# PGTNX05_daisy.net
KiCad netlist of a schematic drawn in EAGLE
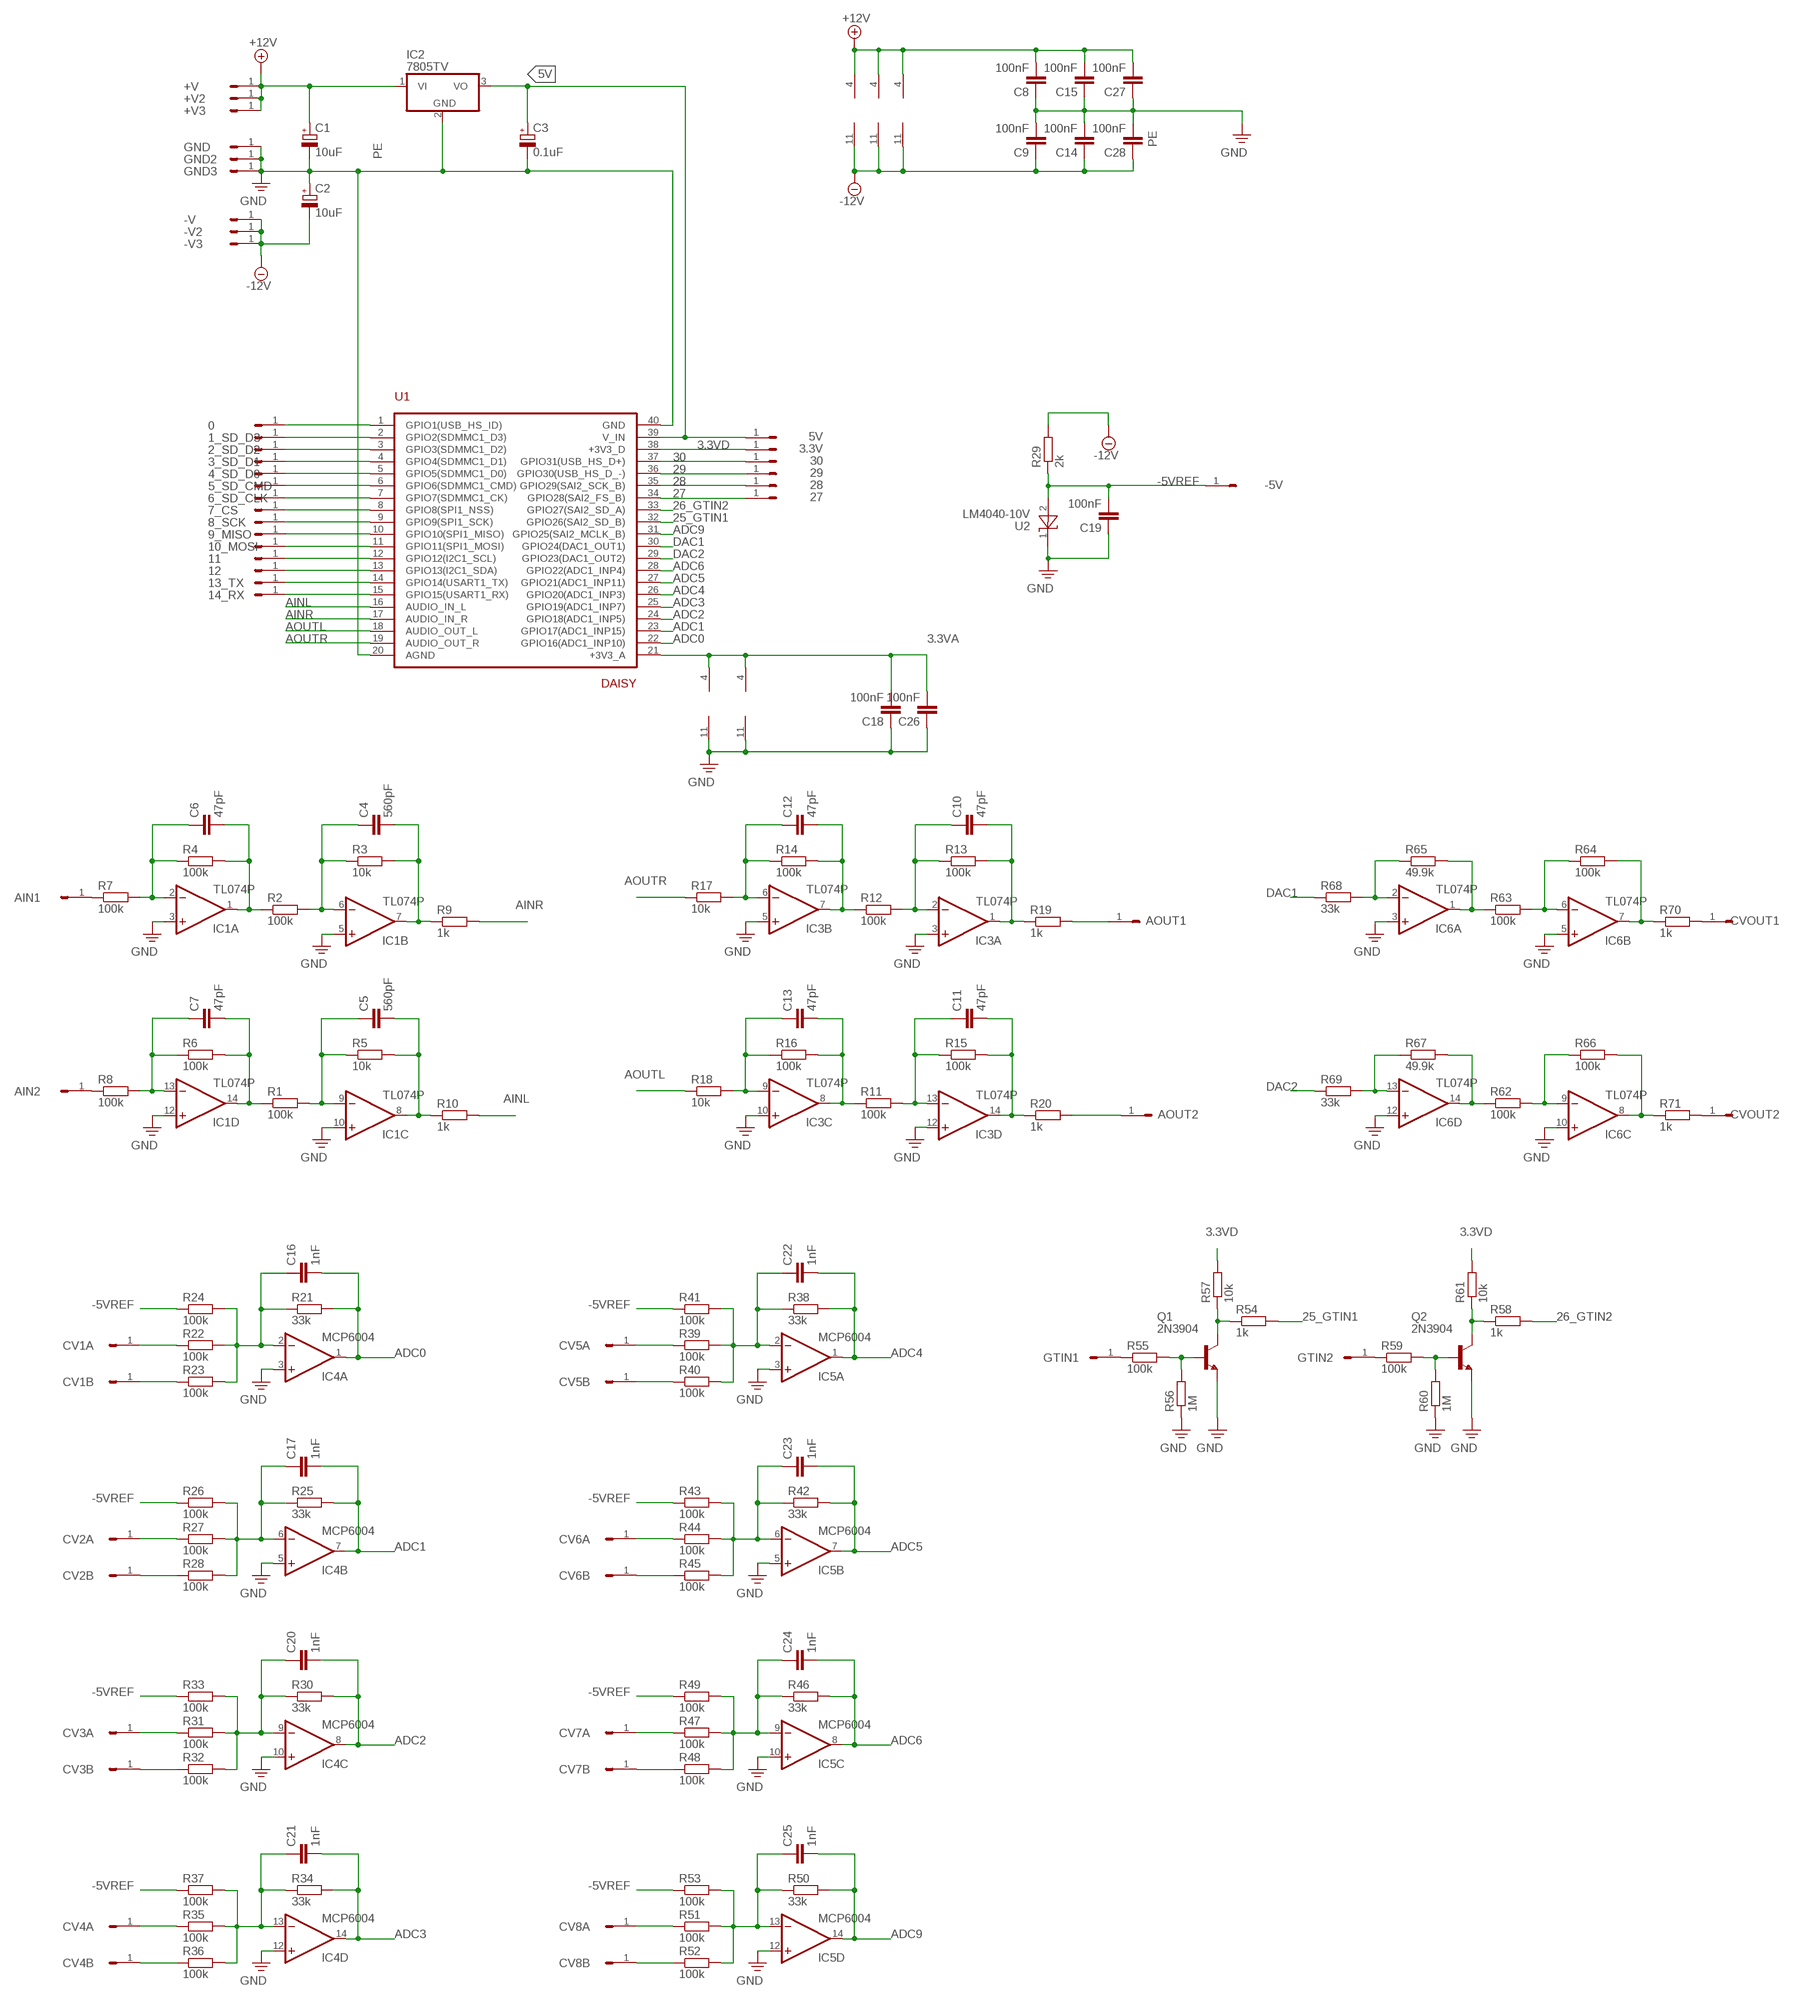
[diagram p0: schematic, sheet 1]

(export (version "E")
  (design (tool "Eeschema 10.0.6"))
  (components
    (comp (ref "+V")
      (value "HEADER/MALE/01")
      (footprint "eagle-import:HEADER_MALE_01")
      (fields (field (name "SPICEPREFIX") "X"))
      (libsource (lib "eagle-import") (part "HEADER/MALE/01"))
    )
    (comp (ref "+V2")
      (value "HEADER/MALE/01")
      (footprint "eagle-import:HEADER_MALE_01")
      (fields (field (name "SPICEPREFIX") "X"))
      (libsource (lib "eagle-import") (part "HEADER/MALE/01"))
    )
    (comp (ref "+V3")
      (value "HEADER/MALE/01")
      (footprint "eagle-import:HEADER_MALE_01")
      (fields (field (name "SPICEPREFIX") "X"))
      (libsource (lib "eagle-import") (part "HEADER/MALE/01"))
    )
    (comp (ref "-5V")
      (value "HEADER/MALE/01")
      (footprint "eagle-import:HEADER_MALE_01")
      (fields (field (name "SPICEPREFIX") "X"))
      (libsource (lib "eagle-import") (part "HEADER/MALE/01"))
    )
    (comp (ref "-V")
      (value "HEADER/MALE/01")
      (footprint "eagle-import:HEADER_MALE_01")
      (fields (field (name "SPICEPREFIX") "X"))
      (libsource (lib "eagle-import") (part "HEADER/MALE/01"))
    )
    (comp (ref "-V2")
      (value "HEADER/MALE/01")
      (footprint "eagle-import:HEADER_MALE_01")
      (fields (field (name "SPICEPREFIX") "X"))
      (libsource (lib "eagle-import") (part "HEADER/MALE/01"))
    )
    (comp (ref "-V3")
      (value "HEADER/MALE/01")
      (footprint "eagle-import:HEADER_MALE_01")
      (fields (field (name "SPICEPREFIX") "X"))
      (libsource (lib "eagle-import") (part "HEADER/MALE/01"))
    )
    (comp (ref "0")
      (value "HEADER/MALE/01")
      (footprint "eagle-import:HEADER_MALE_01")
      (fields (field (name "SPICEPREFIX") "X"))
      (libsource (lib "eagle-import") (part "HEADER/MALE/01"))
    )
    (comp (ref "1_SD_D3")
      (value "HEADER/MALE/01")
      (footprint "eagle-import:HEADER_MALE_01")
      (fields (field (name "SPICEPREFIX") "X"))
      (libsource (lib "eagle-import") (part "HEADER/MALE/01"))
    )
    (comp (ref "2_SD_D2")
      (value "HEADER/MALE/01")
      (footprint "eagle-import:HEADER_MALE_01")
      (fields (field (name "SPICEPREFIX") "X"))
      (libsource (lib "eagle-import") (part "HEADER/MALE/01"))
    )
    (comp (ref "3.3V")
      (value "HEADER/MALE/01")
      (footprint "eagle-import:HEADER_MALE_01")
      (fields (field (name "SPICEPREFIX") "X"))
      (libsource (lib "eagle-import") (part "HEADER/MALE/01"))
    )
    (comp (ref "3_SD_D1")
      (value "HEADER/MALE/01")
      (footprint "eagle-import:HEADER_MALE_01")
      (fields (field (name "SPICEPREFIX") "X"))
      (libsource (lib "eagle-import") (part "HEADER/MALE/01"))
    )
    (comp (ref "4_SD_D0")
      (value "HEADER/MALE/01")
      (footprint "eagle-import:HEADER_MALE_01")
      (fields (field (name "SPICEPREFIX") "X"))
      (libsource (lib "eagle-import") (part "HEADER/MALE/01"))
    )
    (comp (ref "5V")
      (value "HEADER/MALE/01")
      (footprint "eagle-import:HEADER_MALE_01")
      (fields (field (name "SPICEPREFIX") "X"))
      (libsource (lib "eagle-import") (part "HEADER/MALE/01"))
    )
    (comp (ref "5_SD_CMD")
      (value "HEADER/MALE/01")
      (footprint "eagle-import:HEADER_MALE_01")
      (fields (field (name "SPICEPREFIX") "X"))
      (libsource (lib "eagle-import") (part "HEADER/MALE/01"))
    )
    (comp (ref "6_SD_CLK")
      (value "HEADER/MALE/01")
      (footprint "eagle-import:HEADER_MALE_01")
      (fields (field (name "SPICEPREFIX") "X"))
      (libsource (lib "eagle-import") (part "HEADER/MALE/01"))
    )
    (comp (ref "7_CS")
      (value "HEADER/MALE/01")
      (footprint "eagle-import:HEADER_MALE_01")
      (fields (field (name "SPICEPREFIX") "X"))
      (libsource (lib "eagle-import") (part "HEADER/MALE/01"))
    )
    (comp (ref "8_SCK")
      (value "HEADER/MALE/01")
      (footprint "eagle-import:HEADER_MALE_01")
      (fields (field (name "SPICEPREFIX") "X"))
      (libsource (lib "eagle-import") (part "HEADER/MALE/01"))
    )
    (comp (ref "9_MISO")
      (value "HEADER/MALE/01")
      (footprint "eagle-import:HEADER_MALE_01")
      (fields (field (name "SPICEPREFIX") "X"))
      (libsource (lib "eagle-import") (part "HEADER/MALE/01"))
    )
    (comp (ref "10_MOSI")
      (value "HEADER/MALE/01")
      (footprint "eagle-import:HEADER_MALE_01")
      (fields (field (name "SPICEPREFIX") "X"))
      (libsource (lib "eagle-import") (part "HEADER/MALE/01"))
    )
    (comp (ref "11")
      (value "HEADER/MALE/01")
      (footprint "eagle-import:HEADER_MALE_01")
      (fields (field (name "SPICEPREFIX") "X"))
      (libsource (lib "eagle-import") (part "HEADER/MALE/01"))
    )
    (comp (ref "12")
      (value "HEADER/MALE/01")
      (footprint "eagle-import:HEADER_MALE_01")
      (fields (field (name "SPICEPREFIX") "X"))
      (libsource (lib "eagle-import") (part "HEADER/MALE/01"))
    )
    (comp (ref "13_TX")
      (value "HEADER/MALE/01")
      (footprint "eagle-import:HEADER_MALE_01")
      (fields (field (name "SPICEPREFIX") "X"))
      (libsource (lib "eagle-import") (part "HEADER/MALE/01"))
    )
    (comp (ref "14_RX")
      (value "HEADER/MALE/01")
      (footprint "eagle-import:HEADER_MALE_01")
      (fields (field (name "SPICEPREFIX") "X"))
      (libsource (lib "eagle-import") (part "HEADER/MALE/01"))
    )
    (comp (ref "27")
      (value "HEADER/MALE/01")
      (footprint "eagle-import:HEADER_MALE_01")
      (fields (field (name "SPICEPREFIX") "X"))
      (libsource (lib "eagle-import") (part "HEADER/MALE/01"))
    )
    (comp (ref "28")
      (value "HEADER/MALE/01")
      (footprint "eagle-import:HEADER_MALE_01")
      (fields (field (name "SPICEPREFIX") "X"))
      (libsource (lib "eagle-import") (part "HEADER/MALE/01"))
    )
    (comp (ref "29")
      (value "HEADER/MALE/01")
      (footprint "eagle-import:HEADER_MALE_01")
      (fields (field (name "SPICEPREFIX") "X"))
      (libsource (lib "eagle-import") (part "HEADER/MALE/01"))
    )
    (comp (ref "30")
      (value "HEADER/MALE/01")
      (footprint "eagle-import:HEADER_MALE_01")
      (fields (field (name "SPICEPREFIX") "X"))
      (libsource (lib "eagle-import") (part "HEADER/MALE/01"))
    )
    (comp (ref "AIN1")
      (value "HEADER/MALE/01")
      (footprint "eagle-import:HEADER_MALE_01")
      (fields (field (name "SPICEPREFIX") "X"))
      (libsource (lib "eagle-import") (part "HEADER/MALE/01"))
    )
    (comp (ref "AIN2")
      (value "HEADER/MALE/01")
      (footprint "eagle-import:HEADER_MALE_01")
      (fields (field (name "SPICEPREFIX") "X"))
      (libsource (lib "eagle-import") (part "HEADER/MALE/01"))
    )
    (comp (ref "AOUT1")
      (value "HEADER/MALE/01")
      (footprint "eagle-import:HEADER_MALE_01")
      (fields (field (name "SPICEPREFIX") "X"))
      (libsource (lib "eagle-import") (part "HEADER/MALE/01"))
    )
    (comp (ref "AOUT2")
      (value "HEADER/MALE/01")
      (footprint "eagle-import:HEADER_MALE_01")
      (fields (field (name "SPICEPREFIX") "X"))
      (libsource (lib "eagle-import") (part "HEADER/MALE/01"))
    )
    (comp (ref "C1")
      (value "10uF")
      (footprint "eagle-import:E2,5-6")
      (fields (field (name "SPICEPREFIX") "C"))
      (libsource (lib "eagle-import") (part "CAPACITOR/POLARIZEDE2.5-6"))
    )
    (comp (ref "C2")
      (value "10uF")
      (footprint "eagle-import:E2,5-6")
      (fields (field (name "SPICEPREFIX") "C"))
      (libsource (lib "eagle-import") (part "CAPACITOR/POLARIZEDE2.5-6"))
    )
    (comp (ref "C3")
      (value "0.1uF")
      (footprint "eagle-import:E2,5-6")
      (fields (field (name "SPICEPREFIX") "C"))
      (libsource (lib "eagle-import") (part "CAPACITOR/POLARIZEDE2.5-6"))
    )
    (comp (ref "C4")
      (value "560pF")
      (footprint "eagle-import:CERAMICDISC_5")
      (libsource (lib "eagle-import") (part "CAPACITORCERAMICDISC/5"))
    )
    (comp (ref "C5")
      (value "560pF")
      (footprint "eagle-import:CERAMICDISC_5")
      (libsource (lib "eagle-import") (part "CAPACITORCERAMICDISC/5"))
    )
    (comp (ref "C6")
      (value "47pF")
      (footprint "eagle-import:CERAMICDISC_5")
      (libsource (lib "eagle-import") (part "CAPACITORCERAMICDISC/5"))
    )
    (comp (ref "C7")
      (value "47pF")
      (footprint "eagle-import:CERAMICDISC_5")
      (libsource (lib "eagle-import") (part "CAPACITORCERAMICDISC/5"))
    )
    (comp (ref "C8")
      (value "100nF")
      (footprint "eagle-import:CERAMICDISC_5")
      (libsource (lib "eagle-import") (part "CAPACITORCERAMICDISC/5"))
    )
    (comp (ref "C9")
      (value "100nF")
      (footprint "eagle-import:CERAMICDISC_5")
      (libsource (lib "eagle-import") (part "CAPACITORCERAMICDISC/5"))
    )
    (comp (ref "C10")
      (value "47pF")
      (footprint "eagle-import:CERAMICDISC_5")
      (libsource (lib "eagle-import") (part "CAPACITORCERAMICDISC/5"))
    )
    (comp (ref "C11")
      (value "47pF")
      (footprint "eagle-import:CERAMICDISC_5")
      (libsource (lib "eagle-import") (part "CAPACITORCERAMICDISC/5"))
    )
    (comp (ref "C12")
      (value "47pF")
      (footprint "eagle-import:CERAMICDISC_5")
      (libsource (lib "eagle-import") (part "CAPACITORCERAMICDISC/5"))
    )
    (comp (ref "C13")
      (value "47pF")
      (footprint "eagle-import:CERAMICDISC_5")
      (libsource (lib "eagle-import") (part "CAPACITORCERAMICDISC/5"))
    )
    (comp (ref "C14")
      (value "100nF")
      (footprint "eagle-import:CERAMICDISC_5")
      (libsource (lib "eagle-import") (part "CAPACITORCERAMICDISC/5"))
    )
    (comp (ref "C15")
      (value "100nF")
      (footprint "eagle-import:CERAMICDISC_5")
      (libsource (lib "eagle-import") (part "CAPACITORCERAMICDISC/5"))
    )
    (comp (ref "C16")
      (value "1nF")
      (footprint "eagle-import:CERAMICDISC_5")
      (libsource (lib "eagle-import") (part "CAPACITORCERAMICDISC/5"))
    )
    (comp (ref "C17")
      (value "1nF")
      (footprint "eagle-import:CERAMICDISC_5")
      (libsource (lib "eagle-import") (part "CAPACITORCERAMICDISC/5"))
    )
    (comp (ref "C18")
      (value "100nF")
      (footprint "eagle-import:CERAMICDISC_5")
      (libsource (lib "eagle-import") (part "CAPACITORCERAMICDISC/5"))
    )
    (comp (ref "C19")
      (value "100nF")
      (footprint "eagle-import:CERAMICDISC_5")
      (libsource (lib "eagle-import") (part "CAPACITORCERAMICDISC/5"))
    )
    (comp (ref "C20")
      (value "1nF")
      (footprint "eagle-import:CERAMICDISC_5")
      (libsource (lib "eagle-import") (part "CAPACITORCERAMICDISC/5"))
    )
    (comp (ref "C21")
      (value "1nF")
      (footprint "eagle-import:CERAMICDISC_5")
      (libsource (lib "eagle-import") (part "CAPACITORCERAMICDISC/5"))
    )
    (comp (ref "C22")
      (value "1nF")
      (footprint "eagle-import:CERAMICDISC_5")
      (libsource (lib "eagle-import") (part "CAPACITORCERAMICDISC/5"))
    )
    (comp (ref "C23")
      (value "1nF")
      (footprint "eagle-import:CERAMICDISC_5")
      (libsource (lib "eagle-import") (part "CAPACITORCERAMICDISC/5"))
    )
    (comp (ref "C24")
      (value "1nF")
      (footprint "eagle-import:CERAMICDISC_5")
      (libsource (lib "eagle-import") (part "CAPACITORCERAMICDISC/5"))
    )
    (comp (ref "C25")
      (value "1nF")
      (footprint "eagle-import:CERAMICDISC_5")
      (libsource (lib "eagle-import") (part "CAPACITORCERAMICDISC/5"))
    )
    (comp (ref "C26")
      (value "100nF")
      (footprint "eagle-import:CERAMICDISC_5")
      (libsource (lib "eagle-import") (part "CAPACITORCERAMICDISC/5"))
    )
    (comp (ref "C27")
      (value "100nF")
      (footprint "eagle-import:CERAMICDISC_5")
      (libsource (lib "eagle-import") (part "CAPACITORCERAMICDISC/5"))
    )
    (comp (ref "C28")
      (value "100nF")
      (footprint "eagle-import:CERAMICDISC_5")
      (libsource (lib "eagle-import") (part "CAPACITORCERAMICDISC/5"))
    )
    (comp (ref "CV1A")
      (value "HEADER/MALE/01")
      (footprint "eagle-import:HEADER_MALE_01")
      (fields (field (name "SPICEPREFIX") "X"))
      (libsource (lib "eagle-import") (part "HEADER/MALE/01"))
    )
    (comp (ref "CV1B")
      (value "HEADER/MALE/01")
      (footprint "eagle-import:HEADER_MALE_01")
      (fields (field (name "SPICEPREFIX") "X"))
      (libsource (lib "eagle-import") (part "HEADER/MALE/01"))
    )
    (comp (ref "CV2A")
      (value "HEADER/MALE/01")
      (footprint "eagle-import:HEADER_MALE_01")
      (fields (field (name "SPICEPREFIX") "X"))
      (libsource (lib "eagle-import") (part "HEADER/MALE/01"))
    )
    (comp (ref "CV2B")
      (value "HEADER/MALE/01")
      (footprint "eagle-import:HEADER_MALE_01")
      (fields (field (name "SPICEPREFIX") "X"))
      (libsource (lib "eagle-import") (part "HEADER/MALE/01"))
    )
    (comp (ref "CV3A")
      (value "HEADER/MALE/01")
      (footprint "eagle-import:HEADER_MALE_01")
      (fields (field (name "SPICEPREFIX") "X"))
      (libsource (lib "eagle-import") (part "HEADER/MALE/01"))
    )
    (comp (ref "CV3B")
      (value "HEADER/MALE/01")
      (footprint "eagle-import:HEADER_MALE_01")
      (fields (field (name "SPICEPREFIX") "X"))
      (libsource (lib "eagle-import") (part "HEADER/MALE/01"))
    )
    (comp (ref "CV4A")
      (value "HEADER/MALE/01")
      (footprint "eagle-import:HEADER_MALE_01")
      (fields (field (name "SPICEPREFIX") "X"))
      (libsource (lib "eagle-import") (part "HEADER/MALE/01"))
    )
    (comp (ref "CV4B")
      (value "HEADER/MALE/01")
      (footprint "eagle-import:HEADER_MALE_01")
      (fields (field (name "SPICEPREFIX") "X"))
      (libsource (lib "eagle-import") (part "HEADER/MALE/01"))
    )
    (comp (ref "CV5A")
      (value "HEADER/MALE/01")
      (footprint "eagle-import:HEADER_MALE_01")
      (fields (field (name "SPICEPREFIX") "X"))
      (libsource (lib "eagle-import") (part "HEADER/MALE/01"))
    )
    (comp (ref "CV5B")
      (value "HEADER/MALE/01")
      (footprint "eagle-import:HEADER_MALE_01")
      (fields (field (name "SPICEPREFIX") "X"))
      (libsource (lib "eagle-import") (part "HEADER/MALE/01"))
    )
    (comp (ref "CV6A")
      (value "HEADER/MALE/01")
      (footprint "eagle-import:HEADER_MALE_01")
      (fields (field (name "SPICEPREFIX") "X"))
      (libsource (lib "eagle-import") (part "HEADER/MALE/01"))
    )
    (comp (ref "CV6B")
      (value "HEADER/MALE/01")
      (footprint "eagle-import:HEADER_MALE_01")
      (fields (field (name "SPICEPREFIX") "X"))
      (libsource (lib "eagle-import") (part "HEADER/MALE/01"))
    )
    (comp (ref "CV7A")
      (value "HEADER/MALE/01")
      (footprint "eagle-import:HEADER_MALE_01")
      (fields (field (name "SPICEPREFIX") "X"))
      (libsource (lib "eagle-import") (part "HEADER/MALE/01"))
    )
    (comp (ref "CV7B")
      (value "HEADER/MALE/01")
      (footprint "eagle-import:HEADER_MALE_01")
      (fields (field (name "SPICEPREFIX") "X"))
      (libsource (lib "eagle-import") (part "HEADER/MALE/01"))
    )
    (comp (ref "CV8A")
      (value "HEADER/MALE/01")
      (footprint "eagle-import:HEADER_MALE_01")
      (fields (field (name "SPICEPREFIX") "X"))
      (libsource (lib "eagle-import") (part "HEADER/MALE/01"))
    )
    (comp (ref "CV8B")
      (value "HEADER/MALE/01")
      (footprint "eagle-import:HEADER_MALE_01")
      (fields (field (name "SPICEPREFIX") "X"))
      (libsource (lib "eagle-import") (part "HEADER/MALE/01"))
    )
    (comp (ref "CVOUT1")
      (value "HEADER/MALE/01")
      (footprint "eagle-import:HEADER_MALE_01")
      (fields (field (name "SPICEPREFIX") "X"))
      (libsource (lib "eagle-import") (part "HEADER/MALE/01"))
    )
    (comp (ref "CVOUT2")
      (value "HEADER/MALE/01")
      (footprint "eagle-import:HEADER_MALE_01")
      (fields (field (name "SPICEPREFIX") "X"))
      (libsource (lib "eagle-import") (part "HEADER/MALE/01"))
    )
    (comp (ref "GND")
      (value "HEADER/MALE/01")
      (footprint "eagle-import:HEADER_MALE_01")
      (fields (field (name "SPICEPREFIX") "X"))
      (libsource (lib "eagle-import") (part "HEADER/MALE/01"))
    )
    (comp (ref "GND2")
      (value "HEADER/MALE/01")
      (footprint "eagle-import:HEADER_MALE_01")
      (fields (field (name "SPICEPREFIX") "X"))
      (libsource (lib "eagle-import") (part "HEADER/MALE/01"))
    )
    (comp (ref "GND3")
      (value "HEADER/MALE/01")
      (footprint "eagle-import:HEADER_MALE_01")
      (fields (field (name "SPICEPREFIX") "X"))
      (libsource (lib "eagle-import") (part "HEADER/MALE/01"))
    )
    (comp (ref "GTIN1")
      (value "HEADER/MALE/01")
      (footprint "eagle-import:HEADER_MALE_01")
      (fields (field (name "SPICEPREFIX") "X"))
      (libsource (lib "eagle-import") (part "HEADER/MALE/01"))
    )
    (comp (ref "GTIN2")
      (value "HEADER/MALE/01")
      (footprint "eagle-import:HEADER_MALE_01")
      (fields (field (name "SPICEPREFIX") "X"))
      (libsource (lib "eagle-import") (part "HEADER/MALE/01"))
    )
    (comp (ref "IC1")
      (value "TL074P")
      (footprint "eagle-import:DIL14")
      (libsource (lib "eagle-import") (part "TL074P"))
    )
    (comp (ref "IC2")
      (value "7805TV")
      (footprint "eagle-import:TO220V")
      (libsource (lib "eagle-import") (part "78TV05"))
    )
    (comp (ref "IC3")
      (value "TL074P")
      (footprint "eagle-import:DIL14")
      (libsource (lib "eagle-import") (part "TL074P"))
    )
    (comp (ref "IC4")
      (value "MCP6004")
      (footprint "eagle-import:DIL14")
      (libsource (lib "eagle-import") (part "TL074P"))
    )
    (comp (ref "IC5")
      (value "MCP6004")
      (footprint "eagle-import:DIL14")
      (libsource (lib "eagle-import") (part "TL074P"))
    )
    (comp (ref "IC6")
      (value "TL074P")
      (footprint "eagle-import:DIL14")
      (libsource (lib "eagle-import") (part "TL074P"))
    )
    (comp (ref "Q1")
      (value "2N3904")
      (footprint "eagle-import:TO92")
      (libsource (lib "eagle-import") (part "2N3904"))
    )
    (comp (ref "Q2")
      (value "2N3904")
      (footprint "eagle-import:TO92")
      (libsource (lib "eagle-import") (part "2N3904"))
    )
    (comp (ref "R1")
      (value "100k")
      (footprint "eagle-import:RESISTOR_7.5")
      (libsource (lib "eagle-import") (part "RESISTORRESISTOR/UPRIGHT/7.5"))
    )
    (comp (ref "R2")
      (value "100k")
      (footprint "eagle-import:RESISTOR_7.5")
      (libsource (lib "eagle-import") (part "RESISTORRESISTOR/UPRIGHT/7.5"))
    )
    (comp (ref "R3")
      (value "10k")
      (footprint "eagle-import:RESISTOR_7.5")
      (libsource (lib "eagle-import") (part "RESISTORRESISTOR/UPRIGHT/7.5"))
    )
    (comp (ref "R4")
      (value "100k")
      (footprint "eagle-import:RESISTOR_7.5")
      (libsource (lib "eagle-import") (part "RESISTORRESISTOR/UPRIGHT/7.5"))
    )
    (comp (ref "R5")
      (value "10k")
      (footprint "eagle-import:RESISTOR_7.5")
      (libsource (lib "eagle-import") (part "RESISTORRESISTOR/UPRIGHT/7.5"))
    )
    (comp (ref "R6")
      (value "100k")
      (footprint "eagle-import:RESISTOR_7.5")
      (libsource (lib "eagle-import") (part "RESISTORRESISTOR/UPRIGHT/7.5"))
    )
    (comp (ref "R7")
      (value "100k")
      (footprint "eagle-import:RESISTOR_7.5")
      (libsource (lib "eagle-import") (part "RESISTORRESISTOR/UPRIGHT/7.5"))
    )
    (comp (ref "R8")
      (value "100k")
      (footprint "eagle-import:RESISTOR_7.5")
      (libsource (lib "eagle-import") (part "RESISTORRESISTOR/UPRIGHT/7.5"))
    )
    (comp (ref "R9")
      (value "1k")
      (footprint "eagle-import:RESISTOR_7.5")
      (libsource (lib "eagle-import") (part "RESISTORRESISTOR/UPRIGHT/7.5"))
    )
    (comp (ref "R10")
      (value "1k")
      (footprint "eagle-import:RESISTOR_7.5")
      (libsource (lib "eagle-import") (part "RESISTORRESISTOR/UPRIGHT/7.5"))
    )
    (comp (ref "R11")
      (value "100k")
      (footprint "eagle-import:RESISTOR_7.5")
      (libsource (lib "eagle-import") (part "RESISTORRESISTOR/UPRIGHT/7.5"))
    )
    (comp (ref "R12")
      (value "100k")
      (footprint "eagle-import:RESISTOR_7.5")
      (libsource (lib "eagle-import") (part "RESISTORRESISTOR/UPRIGHT/7.5"))
    )
    (comp (ref "R13")
      (value "100k")
      (footprint "eagle-import:RESISTOR_7.5")
      (libsource (lib "eagle-import") (part "RESISTORRESISTOR/UPRIGHT/7.5"))
    )
    (comp (ref "R14")
      (value "100k")
      (footprint "eagle-import:RESISTOR_7.5")
      (libsource (lib "eagle-import") (part "RESISTORRESISTOR/UPRIGHT/7.5"))
    )
    (comp (ref "R15")
      (value "100k")
      (footprint "eagle-import:RESISTOR_7.5")
      (libsource (lib "eagle-import") (part "RESISTORRESISTOR/UPRIGHT/7.5"))
    )
    (comp (ref "R16")
      (value "100k")
      (footprint "eagle-import:RESISTOR_7.5")
      (libsource (lib "eagle-import") (part "RESISTORRESISTOR/UPRIGHT/7.5"))
    )
    (comp (ref "R17")
      (value "10k")
      (footprint "eagle-import:RESISTOR_7.5")
      (libsource (lib "eagle-import") (part "RESISTORRESISTOR/UPRIGHT/7.5"))
    )
    (comp (ref "R18")
      (value "10k")
      (footprint "eagle-import:RESISTOR_7.5")
      (libsource (lib "eagle-import") (part "RESISTORRESISTOR/UPRIGHT/7.5"))
    )
    (comp (ref "R19")
      (value "1k")
      (footprint "eagle-import:RESISTOR_7.5")
      (libsource (lib "eagle-import") (part "RESISTORRESISTOR/UPRIGHT/7.5"))
    )
    (comp (ref "R20")
      (value "1k")
      (footprint "eagle-import:RESISTOR_7.5")
      (libsource (lib "eagle-import") (part "RESISTORRESISTOR/UPRIGHT/7.5"))
    )
    (comp (ref "R21")
      (value "33k")
      (footprint "eagle-import:RESISTOR_7.5")
      (libsource (lib "eagle-import") (part "RESISTORRESISTOR/UPRIGHT/7.5"))
    )
    (comp (ref "R22")
      (value "100k")
      (footprint "eagle-import:RESISTOR_7.5")
      (libsource (lib "eagle-import") (part "RESISTORRESISTOR/UPRIGHT/7.5"))
    )
    (comp (ref "R23")
      (value "100k")
      (footprint "eagle-import:RESISTOR_7.5")
      (libsource (lib "eagle-import") (part "RESISTORRESISTOR/UPRIGHT/7.5"))
    )
    (comp (ref "R24")
      (value "100k")
      (footprint "eagle-import:RESISTOR_7.5")
      (libsource (lib "eagle-import") (part "RESISTORRESISTOR/UPRIGHT/7.5"))
    )
    (comp (ref "R25")
      (value "33k")
      (footprint "eagle-import:RESISTOR_7.5")
      (libsource (lib "eagle-import") (part "RESISTORRESISTOR/UPRIGHT/7.5"))
    )
    (comp (ref "R26")
      (value "100k")
      (footprint "eagle-import:RESISTOR_7.5")
      (libsource (lib "eagle-import") (part "RESISTORRESISTOR/UPRIGHT/7.5"))
    )
    (comp (ref "R27")
      (value "100k")
      (footprint "eagle-import:RESISTOR_7.5")
      (libsource (lib "eagle-import") (part "RESISTORRESISTOR/UPRIGHT/7.5"))
    )
    (comp (ref "R28")
      (value "100k")
      (footprint "eagle-import:RESISTOR_7.5")
      (libsource (lib "eagle-import") (part "RESISTORRESISTOR/UPRIGHT/7.5"))
    )
    (comp (ref "R29")
      (value "2k")
      (footprint "eagle-import:RESISTOR_7.5")
      (libsource (lib "eagle-import") (part "RESISTORRESISTOR/UPRIGHT/7.5"))
    )
    (comp (ref "R30")
      (value "33k")
      (footprint "eagle-import:RESISTOR_7.5")
      (libsource (lib "eagle-import") (part "RESISTORRESISTOR/UPRIGHT/7.5"))
    )
    (comp (ref "R31")
      (value "100k")
      (footprint "eagle-import:RESISTOR_7.5")
      (libsource (lib "eagle-import") (part "RESISTORRESISTOR/UPRIGHT/7.5"))
    )
    (comp (ref "R32")
      (value "100k")
      (footprint "eagle-import:RESISTOR_7.5")
      (libsource (lib "eagle-import") (part "RESISTORRESISTOR/UPRIGHT/7.5"))
    )
    (comp (ref "R33")
      (value "100k")
      (footprint "eagle-import:RESISTOR_7.5")
      (libsource (lib "eagle-import") (part "RESISTORRESISTOR/UPRIGHT/7.5"))
    )
    (comp (ref "R34")
      (value "33k")
      (footprint "eagle-import:RESISTOR_7.5")
      (libsource (lib "eagle-import") (part "RESISTORRESISTOR/UPRIGHT/7.5"))
    )
    (comp (ref "R35")
      (value "100k")
      (footprint "eagle-import:RESISTOR_7.5")
      (libsource (lib "eagle-import") (part "RESISTORRESISTOR/UPRIGHT/7.5"))
    )
    (comp (ref "R36")
      (value "100k")
      (footprint "eagle-import:RESISTOR_7.5")
      (libsource (lib "eagle-import") (part "RESISTORRESISTOR/UPRIGHT/7.5"))
    )
    (comp (ref "R37")
      (value "100k")
      (footprint "eagle-import:RESISTOR_7.5")
      (libsource (lib "eagle-import") (part "RESISTORRESISTOR/UPRIGHT/7.5"))
    )
    (comp (ref "R38")
      (value "33k")
      (footprint "eagle-import:RESISTOR_7.5")
      (libsource (lib "eagle-import") (part "RESISTORRESISTOR/UPRIGHT/7.5"))
    )
    (comp (ref "R39")
      (value "100k")
      (footprint "eagle-import:RESISTOR_7.5")
      (libsource (lib "eagle-import") (part "RESISTORRESISTOR/UPRIGHT/7.5"))
    )
    (comp (ref "R40")
      (value "100k")
      (footprint "eagle-import:RESISTOR_7.5")
      (libsource (lib "eagle-import") (part "RESISTORRESISTOR/UPRIGHT/7.5"))
    )
    (comp (ref "R41")
      (value "100k")
      (footprint "eagle-import:RESISTOR_7.5")
      (libsource (lib "eagle-import") (part "RESISTORRESISTOR/UPRIGHT/7.5"))
    )
    (comp (ref "R42")
      (value "33k")
      (footprint "eagle-import:RESISTOR_7.5")
      (libsource (lib "eagle-import") (part "RESISTORRESISTOR/UPRIGHT/7.5"))
    )
    (comp (ref "R43")
      (value "100k")
      (footprint "eagle-import:RESISTOR_7.5")
      (libsource (lib "eagle-import") (part "RESISTORRESISTOR/UPRIGHT/7.5"))
    )
    (comp (ref "R44")
      (value "100k")
      (footprint "eagle-import:RESISTOR_7.5")
      (libsource (lib "eagle-import") (part "RESISTORRESISTOR/UPRIGHT/7.5"))
    )
    (comp (ref "R45")
      (value "100k")
      (footprint "eagle-import:RESISTOR_7.5")
      (libsource (lib "eagle-import") (part "RESISTORRESISTOR/UPRIGHT/7.5"))
    )
    (comp (ref "R46")
      (value "33k")
      (footprint "eagle-import:RESISTOR_7.5")
      (libsource (lib "eagle-import") (part "RESISTORRESISTOR/UPRIGHT/7.5"))
    )
    (comp (ref "R47")
      (value "100k")
      (footprint "eagle-import:RESISTOR_7.5")
      (libsource (lib "eagle-import") (part "RESISTORRESISTOR/UPRIGHT/7.5"))
    )
    (comp (ref "R48")
      (value "100k")
      (footprint "eagle-import:RESISTOR_7.5")
      (libsource (lib "eagle-import") (part "RESISTORRESISTOR/UPRIGHT/7.5"))
    )
    (comp (ref "R49")
      (value "100k")
      (footprint "eagle-import:RESISTOR_7.5")
      (libsource (lib "eagle-import") (part "RESISTORRESISTOR/UPRIGHT/7.5"))
    )
    (comp (ref "R50")
      (value "33k")
      (footprint "eagle-import:RESISTOR_7.5")
      (libsource (lib "eagle-import") (part "RESISTORRESISTOR/UPRIGHT/7.5"))
    )
    (comp (ref "R51")
      (value "100k")
      (footprint "eagle-import:RESISTOR_7.5")
      (libsource (lib "eagle-import") (part "RESISTORRESISTOR/UPRIGHT/7.5"))
    )
    (comp (ref "R52")
      (value "100k")
      (footprint "eagle-import:RESISTOR_7.5")
      (libsource (lib "eagle-import") (part "RESISTORRESISTOR/UPRIGHT/7.5"))
    )
    (comp (ref "R53")
      (value "100k")
      (footprint "eagle-import:RESISTOR_7.5")
      (libsource (lib "eagle-import") (part "RESISTORRESISTOR/UPRIGHT/7.5"))
    )
    (comp (ref "R54")
      (value "1k")
      (footprint "eagle-import:RESISTOR_7.5")
      (libsource (lib "eagle-import") (part "RESISTORRESISTOR/UPRIGHT/7.5"))
    )
    (comp (ref "R55")
      (value "100k")
      (footprint "eagle-import:RESISTOR_7.5")
      (libsource (lib "eagle-import") (part "RESISTORRESISTOR/UPRIGHT/7.5"))
    )
    (comp (ref "R56")
      (value "1M")
      (footprint "eagle-import:RESISTOR_7.5")
      (libsource (lib "eagle-import") (part "RESISTORRESISTOR/UPRIGHT/7.5"))
    )
    (comp (ref "R57")
      (value "10k")
      (footprint "eagle-import:RESISTOR_7.5")
      (libsource (lib "eagle-import") (part "RESISTORRESISTOR/UPRIGHT/7.5"))
    )
    (comp (ref "R58")
      (value "1k")
      (footprint "eagle-import:RESISTOR_7.5")
      (libsource (lib "eagle-import") (part "RESISTORRESISTOR/UPRIGHT/7.5"))
    )
    (comp (ref "R59")
      (value "100k")
      (footprint "eagle-import:RESISTOR_7.5")
      (libsource (lib "eagle-import") (part "RESISTORRESISTOR/UPRIGHT/7.5"))
    )
    (comp (ref "R60")
      (value "1M")
      (footprint "eagle-import:RESISTOR_7.5")
      (libsource (lib "eagle-import") (part "RESISTORRESISTOR/UPRIGHT/7.5"))
    )
    (comp (ref "R61")
      (value "10k")
      (footprint "eagle-import:RESISTOR_7.5")
      (libsource (lib "eagle-import") (part "RESISTORRESISTOR/UPRIGHT/7.5"))
    )
    (comp (ref "R62")
      (value "100k")
      (footprint "eagle-import:RESISTOR_7.5")
      (libsource (lib "eagle-import") (part "RESISTORRESISTOR/UPRIGHT/7.5"))
    )
    (comp (ref "R63")
      (value "100k")
      (footprint "eagle-import:RESISTOR_7.5")
      (libsource (lib "eagle-import") (part "RESISTORRESISTOR/UPRIGHT/7.5"))
    )
    (comp (ref "R64")
      (value "100k")
      (footprint "eagle-import:RESISTOR_7.5")
      (libsource (lib "eagle-import") (part "RESISTORRESISTOR/UPRIGHT/7.5"))
    )
    (comp (ref "R65")
      (value "49.9k")
      (footprint "eagle-import:RESISTOR_7.5")
      (libsource (lib "eagle-import") (part "RESISTORRESISTOR/UPRIGHT/7.5"))
    )
    (comp (ref "R66")
      (value "100k")
      (footprint "eagle-import:RESISTOR_7.5")
      (libsource (lib "eagle-import") (part "RESISTORRESISTOR/UPRIGHT/7.5"))
    )
    (comp (ref "R67")
      (value "49.9k")
      (footprint "eagle-import:RESISTOR_7.5")
      (libsource (lib "eagle-import") (part "RESISTORRESISTOR/UPRIGHT/7.5"))
    )
    (comp (ref "R68")
      (value "33k")
      (footprint "eagle-import:RESISTOR_7.5")
      (libsource (lib "eagle-import") (part "RESISTORRESISTOR/UPRIGHT/7.5"))
    )
    (comp (ref "R69")
      (value "33k")
      (footprint "eagle-import:RESISTOR_7.5")
      (libsource (lib "eagle-import") (part "RESISTORRESISTOR/UPRIGHT/7.5"))
    )
    (comp (ref "R70")
      (value "1k")
      (footprint "eagle-import:RESISTOR_7.5")
      (libsource (lib "eagle-import") (part "RESISTORRESISTOR/UPRIGHT/7.5"))
    )
    (comp (ref "R71")
      (value "1k")
      (footprint "eagle-import:RESISTOR_7.5")
      (libsource (lib "eagle-import") (part "RESISTORRESISTOR/UPRIGHT/7.5"))
    )
    (comp (ref "U1")
      (value "DAISY")
      (footprint "eagle-import:ES_DAISY_SEED")
      (libsource (lib "eagle-import") (part "ES_DAISY_SEED_REV4"))
    )
    (comp (ref "U2")
      (value "LM4040-10V")
      (footprint "eagle-import:SOT-23")
      (libsource (lib "eagle-import") (part "LM4040CYM3-2.5"))
    )
  )
  (nets
    (net (code "1") (name "+12V") (class "Default")
      (node (ref "+V") (pin "1") (pinfunction "3_1") (pintype "passive"))
      (node (ref "+V2") (pin "1") (pinfunction "3_1") (pintype "passive"))
      (node (ref "+V3") (pin "1") (pinfunction "3_1") (pintype "passive"))
      (node (ref "C1") (pin "+") (pinfunction "+_+") (pintype "passive"))
      (node (ref "C15") (pin "2") (pinfunction "2_2") (pintype "passive"))
      (node (ref "C27") (pin "2") (pinfunction "2_2") (pintype "passive"))
      (node (ref "C8") (pin "2") (pinfunction "2_2") (pintype "passive"))
      (node (ref "IC1") (pin "4") (pinfunction "V+_4") (pintype "power_in"))
      (node (ref "IC2") (pin "1") (pinfunction "VI_1") (pintype "input"))
      (node (ref "IC3") (pin "4") (pinfunction "V+_4") (pintype "power_in"))
      (node (ref "IC6") (pin "4") (pinfunction "V+_4") (pintype "power_in"))
    )
    (net (code "2") (name "-12V") (class "Default")
      (node (ref "-V") (pin "1") (pinfunction "3_1") (pintype "passive"))
      (node (ref "-V2") (pin "1") (pinfunction "3_1") (pintype "passive"))
      (node (ref "-V3") (pin "1") (pinfunction "3_1") (pintype "passive"))
      (node (ref "C14") (pin "1") (pinfunction "1_1") (pintype "passive"))
      (node (ref "C2") (pin "-") (pinfunction "-_-") (pintype "passive"))
      (node (ref "C28") (pin "1") (pinfunction "1_1") (pintype "passive"))
      (node (ref "C9") (pin "1") (pinfunction "1_1") (pintype "passive"))
      (node (ref "IC1") (pin "11") (pinfunction "V-_11") (pintype "power_in"))
      (node (ref "IC3") (pin "11") (pinfunction "V-_11") (pintype "power_in"))
      (node (ref "IC6") (pin "11") (pinfunction "V-_11") (pintype "power_in"))
      (node (ref "R29") (pin "2") (pinfunction "2_2") (pintype "passive"))
    )
    (net (code "3") (name "/-5VREF") (class "Default")
      (node (ref "-5V") (pin "1") (pinfunction "3_1") (pintype "passive"))
      (node (ref "C19") (pin "2") (pinfunction "2_2") (pintype "passive"))
      (node (ref "R24") (pin "1") (pinfunction "1_1") (pintype "passive"))
      (node (ref "R26") (pin "1") (pinfunction "1_1") (pintype "passive"))
      (node (ref "R29") (pin "1") (pinfunction "1_1") (pintype "passive"))
      (node (ref "R33") (pin "1") (pinfunction "1_1") (pintype "passive"))
      (node (ref "R37") (pin "1") (pinfunction "1_1") (pintype "passive"))
      (node (ref "R41") (pin "1") (pinfunction "1_1") (pintype "passive"))
      (node (ref "R43") (pin "1") (pinfunction "1_1") (pintype "passive"))
      (node (ref "R49") (pin "1") (pinfunction "1_1") (pintype "passive"))
      (node (ref "R53") (pin "1") (pinfunction "1_1") (pintype "passive"))
      (node (ref "U2") (pin "2") (pinfunction "A_2") (pintype "output"))
    )
    (net (code "4") (name "/3.3VA") (class "Default")
      (node (ref "C18") (pin "2") (pinfunction "2_2") (pintype "passive"))
      (node (ref "C26") (pin "2") (pinfunction "2_2") (pintype "passive"))
      (node (ref "IC4") (pin "4") (pinfunction "V+_4") (pintype "power_in"))
      (node (ref "IC5") (pin "4") (pinfunction "V+_4") (pintype "power_in"))
      (node (ref "U1") (pin "21") (pinfunction "+3V3_A_21") (pintype "bidirectional"))
    )
    (net (code "5") (name "/3.3VD") (class "Default")
      (node (ref "3.3V") (pin "1") (pinfunction "3_1") (pintype "passive"))
      (node (ref "R57") (pin "2") (pinfunction "2_2") (pintype "passive"))
      (node (ref "R61") (pin "2") (pinfunction "2_2") (pintype "passive"))
      (node (ref "U1") (pin "38") (pinfunction "+3V3_D_38") (pintype "bidirectional"))
    )
    (net (code "6") (name "/25_GTIN1") (class "Default")
      (node (ref "R54") (pin "2") (pinfunction "2_2") (pintype "passive"))
      (node (ref "U1") (pin "32") (pinfunction "GPIO26(SAI2_SD_B)_32") (pintype "bidirectional"))
    )
    (net (code "7") (name "/26_GTIN2") (class "Default")
      (node (ref "R58") (pin "2") (pinfunction "2_2") (pintype "passive"))
      (node (ref "U1") (pin "33") (pinfunction "GPIO27(SAI2_SD_A)_33") (pintype "bidirectional"))
    )
    (net (code "8") (name "/27") (class "Default")
      (node (ref "27") (pin "1") (pinfunction "3_1") (pintype "passive"))
      (node (ref "U1") (pin "34") (pinfunction "GPIO28(SAI2_FS_B)_34") (pintype "bidirectional"))
    )
    (net (code "9") (name "/28") (class "Default")
      (node (ref "28") (pin "1") (pinfunction "3_1") (pintype "passive"))
      (node (ref "U1") (pin "35") (pinfunction "GPIO29(SAI2_SCK_B)_35") (pintype "bidirectional"))
    )
    (net (code "10") (name "/29") (class "Default")
      (node (ref "29") (pin "1") (pinfunction "3_1") (pintype "passive"))
      (node (ref "U1") (pin "36") (pinfunction "GPIO30(USB_HS_D_-)_36") (pintype "bidirectional"))
    )
    (net (code "11") (name "/30") (class "Default")
      (node (ref "30") (pin "1") (pinfunction "3_1") (pintype "passive"))
      (node (ref "U1") (pin "37") (pinfunction "GPIO31(USB_HS_D+)_37") (pintype "bidirectional"))
    )
    (net (code "12") (name "/ADC0") (class "Default")
      (node (ref "C16") (pin "2") (pinfunction "2_2") (pintype "passive"))
      (node (ref "IC4") (pin "1") (pinfunction "OUT_1") (pintype "output"))
      (node (ref "R21") (pin "2") (pinfunction "2_2") (pintype "passive"))
      (node (ref "U1") (pin "22") (pinfunction "GPIO16(ADC1_INP10)_22") (pintype "bidirectional"))
    )
    (net (code "13") (name "/ADC1") (class "Default")
      (node (ref "C17") (pin "2") (pinfunction "2_2") (pintype "passive"))
      (node (ref "IC4") (pin "7") (pinfunction "OUT_7") (pintype "output"))
      (node (ref "R25") (pin "2") (pinfunction "2_2") (pintype "passive"))
      (node (ref "U1") (pin "23") (pinfunction "GPIO17(ADC1_INP15)_23") (pintype "bidirectional"))
    )
    (net (code "14") (name "/ADC2") (class "Default")
      (node (ref "C20") (pin "2") (pinfunction "2_2") (pintype "passive"))
      (node (ref "IC4") (pin "8") (pinfunction "OUT_8") (pintype "output"))
      (node (ref "R30") (pin "2") (pinfunction "2_2") (pintype "passive"))
      (node (ref "U1") (pin "24") (pinfunction "GPIO18(ADC1_INP5)_24") (pintype "bidirectional"))
    )
    (net (code "15") (name "/ADC3") (class "Default")
      (node (ref "C21") (pin "2") (pinfunction "2_2") (pintype "passive"))
      (node (ref "IC4") (pin "14") (pinfunction "OUT_14") (pintype "output"))
      (node (ref "R34") (pin "2") (pinfunction "2_2") (pintype "passive"))
      (node (ref "U1") (pin "25") (pinfunction "GPIO19(ADC1_INP7)_25") (pintype "bidirectional"))
    )
    (net (code "16") (name "/ADC4") (class "Default")
      (node (ref "C22") (pin "2") (pinfunction "2_2") (pintype "passive"))
      (node (ref "IC5") (pin "1") (pinfunction "OUT_1") (pintype "output"))
      (node (ref "R38") (pin "2") (pinfunction "2_2") (pintype "passive"))
      (node (ref "U1") (pin "26") (pinfunction "GPIO20(ADC1_INP3)_26") (pintype "bidirectional"))
    )
    (net (code "17") (name "/ADC5") (class "Default")
      (node (ref "C23") (pin "2") (pinfunction "2_2") (pintype "passive"))
      (node (ref "IC5") (pin "7") (pinfunction "OUT_7") (pintype "output"))
      (node (ref "R42") (pin "2") (pinfunction "2_2") (pintype "passive"))
      (node (ref "U1") (pin "27") (pinfunction "GPIO21(ADC1_INP11)_27") (pintype "bidirectional"))
    )
    (net (code "18") (name "/ADC6") (class "Default")
      (node (ref "C24") (pin "2") (pinfunction "2_2") (pintype "passive"))
      (node (ref "IC5") (pin "8") (pinfunction "OUT_8") (pintype "output"))
      (node (ref "R46") (pin "2") (pinfunction "2_2") (pintype "passive"))
      (node (ref "U1") (pin "28") (pinfunction "GPIO22(ADC1_INP4)_28") (pintype "bidirectional"))
    )
    (net (code "19") (name "/ADC9") (class "Default")
      (node (ref "C25") (pin "2") (pinfunction "2_2") (pintype "passive"))
      (node (ref "IC5") (pin "14") (pinfunction "OUT_14") (pintype "output"))
      (node (ref "R50") (pin "2") (pinfunction "2_2") (pintype "passive"))
      (node (ref "U1") (pin "31") (pinfunction "GPIO25(SAI2_MCLK_B)_31") (pintype "bidirectional"))
    )
    (net (code "20") (name "/AINL") (class "Default")
      (node (ref "R10") (pin "2") (pinfunction "2_2") (pintype "passive"))
      (node (ref "U1") (pin "16") (pinfunction "AUDIO_IN_L_16") (pintype "bidirectional"))
    )
    (net (code "21") (name "/AINR") (class "Default")
      (node (ref "R9") (pin "2") (pinfunction "2_2") (pintype "passive"))
      (node (ref "U1") (pin "17") (pinfunction "AUDIO_IN_R_17") (pintype "bidirectional"))
    )
    (net (code "22") (name "/AOUTL") (class "Default")
      (node (ref "R18") (pin "1") (pinfunction "1_1") (pintype "passive"))
      (node (ref "U1") (pin "18") (pinfunction "AUDIO_OUT_L_18") (pintype "bidirectional"))
    )
    (net (code "23") (name "/AOUTR") (class "Default")
      (node (ref "R17") (pin "1") (pinfunction "1_1") (pintype "passive"))
      (node (ref "U1") (pin "19") (pinfunction "AUDIO_OUT_R_19") (pintype "bidirectional"))
    )
    (net (code "24") (name "/DAC1") (class "Default")
      (node (ref "R68") (pin "1") (pinfunction "1_1") (pintype "passive"))
      (node (ref "U1") (pin "30") (pinfunction "GPIO24(DAC1_OUT1)_30") (pintype "bidirectional"))
    )
    (net (code "25") (name "/DAC2") (class "Default")
      (node (ref "R69") (pin "1") (pinfunction "1_1") (pintype "passive"))
      (node (ref "U1") (pin "29") (pinfunction "GPIO23(DAC1_OUT2)_29") (pintype "bidirectional"))
    )
    (net (code "26") (name "5V") (class "Default")
      (node (ref "5V") (pin "1") (pinfunction "3_1") (pintype "passive"))
      (node (ref "C3") (pin "+") (pinfunction "+_+") (pintype "passive"))
      (node (ref "IC2") (pin "3") (pinfunction "VO_3") (pintype "passive"))
      (node (ref "U1") (pin "39") (pinfunction "V_IN_39") (pintype "bidirectional"))
    )
    (net (code "27") (name "GND") (class "Default")
      (node (ref "C1") (pin "-") (pinfunction "-_-") (pintype "passive"))
      (node (ref "C14") (pin "2") (pinfunction "2_2") (pintype "passive"))
      (node (ref "C15") (pin "1") (pinfunction "1_1") (pintype "passive"))
      (node (ref "C18") (pin "1") (pinfunction "1_1") (pintype "passive"))
      (node (ref "C19") (pin "1") (pinfunction "1_1") (pintype "passive"))
      (node (ref "C2") (pin "+") (pinfunction "+_+") (pintype "passive"))
      (node (ref "C26") (pin "1") (pinfunction "1_1") (pintype "passive"))
      (node (ref "C27") (pin "1") (pinfunction "1_1") (pintype "passive"))
      (node (ref "C28") (pin "2") (pinfunction "2_2") (pintype "passive"))
      (node (ref "C3") (pin "-") (pinfunction "-_-") (pintype "passive"))
      (node (ref "C8") (pin "1") (pinfunction "1_1") (pintype "passive"))
      (node (ref "C9") (pin "2") (pinfunction "2_2") (pintype "passive"))
      (node (ref "GND") (pin "1") (pinfunction "3_1") (pintype "passive"))
      (node (ref "GND2") (pin "1") (pinfunction "3_1") (pintype "passive"))
      (node (ref "GND3") (pin "1") (pinfunction "3_1") (pintype "passive"))
      (node (ref "IC1") (pin "10") (pinfunction "+IN_10") (pintype "input"))
      (node (ref "IC1") (pin "12") (pinfunction "+IN_12") (pintype "input"))
      (node (ref "IC1") (pin "3") (pinfunction "+IN_3") (pintype "input"))
      (node (ref "IC1") (pin "5") (pinfunction "+IN_5") (pintype "input"))
      (node (ref "IC2") (pin "2") (pinfunction "GND_2") (pintype "passive"))
      (node (ref "IC3") (pin "10") (pinfunction "+IN_10") (pintype "input"))
      (node (ref "IC3") (pin "12") (pinfunction "+IN_12") (pintype "input"))
      (node (ref "IC3") (pin "3") (pinfunction "+IN_3") (pintype "input"))
      (node (ref "IC3") (pin "5") (pinfunction "+IN_5") (pintype "input"))
      (node (ref "IC4") (pin "10") (pinfunction "+IN_10") (pintype "input"))
      (node (ref "IC4") (pin "11") (pinfunction "V-_11") (pintype "power_in"))
      (node (ref "IC4") (pin "12") (pinfunction "+IN_12") (pintype "input"))
      (node (ref "IC4") (pin "3") (pinfunction "+IN_3") (pintype "input"))
      (node (ref "IC4") (pin "5") (pinfunction "+IN_5") (pintype "input"))
      (node (ref "IC5") (pin "10") (pinfunction "+IN_10") (pintype "input"))
      (node (ref "IC5") (pin "11") (pinfunction "V-_11") (pintype "power_in"))
      (node (ref "IC5") (pin "12") (pinfunction "+IN_12") (pintype "input"))
      (node (ref "IC5") (pin "3") (pinfunction "+IN_3") (pintype "input"))
      (node (ref "IC5") (pin "5") (pinfunction "+IN_5") (pintype "input"))
      (node (ref "IC6") (pin "10") (pinfunction "+IN_10") (pintype "input"))
      (node (ref "IC6") (pin "12") (pinfunction "+IN_12") (pintype "input"))
      (node (ref "IC6") (pin "3") (pinfunction "+IN_3") (pintype "input"))
      (node (ref "IC6") (pin "5") (pinfunction "+IN_5") (pintype "input"))
      (node (ref "Q1") (pin "3") (pinfunction "E_3") (pintype "passive"))
      (node (ref "Q2") (pin "3") (pinfunction "E_3") (pintype "passive"))
      (node (ref "R56") (pin "1") (pinfunction "1_1") (pintype "passive"))
      (node (ref "R60") (pin "1") (pinfunction "1_1") (pintype "passive"))
      (node (ref "U1") (pin "20") (pinfunction "AGND_20") (pintype "bidirectional"))
      (node (ref "U1") (pin "40") (pinfunction "GND_40") (pintype "bidirectional"))
      (node (ref "U2") (pin "1") (pinfunction "C_1") (pintype "input"))
    )
    (net (code "28") (name "Net-(0-3)") (class "Default")
      (node (ref "0") (pin "1") (pinfunction "3_1") (pintype "passive"))
      (node (ref "U1") (pin "1") (pinfunction "GPIO1(USB_HS_ID)_1") (pintype "bidirectional"))
    )
    (net (code "29") (name "Net-(1_SD_D3-3)") (class "Default")
      (node (ref "1_SD_D3") (pin "1") (pinfunction "3_1") (pintype "passive"))
      (node (ref "U1") (pin "2") (pinfunction "GPIO2(SDMMC1_D3)_2") (pintype "bidirectional"))
    )
    (net (code "30") (name "Net-(2_SD_D2-3)") (class "Default")
      (node (ref "2_SD_D2") (pin "1") (pinfunction "3_1") (pintype "passive"))
      (node (ref "U1") (pin "3") (pinfunction "GPIO3(SDMMC1_D2)_3") (pintype "bidirectional"))
    )
    (net (code "31") (name "Net-(3_SD_D1-3)") (class "Default")
      (node (ref "3_SD_D1") (pin "1") (pinfunction "3_1") (pintype "passive"))
      (node (ref "U1") (pin "4") (pinfunction "GPIO4(SDMMC1_D1)_4") (pintype "bidirectional"))
    )
    (net (code "32") (name "Net-(4_SD_D0-3)") (class "Default")
      (node (ref "4_SD_D0") (pin "1") (pinfunction "3_1") (pintype "passive"))
      (node (ref "U1") (pin "5") (pinfunction "GPIO5(SDMMC1_D0)_5") (pintype "bidirectional"))
    )
    (net (code "33") (name "Net-(5_SD_CMD-3)") (class "Default")
      (node (ref "5_SD_CMD") (pin "1") (pinfunction "3_1") (pintype "passive"))
      (node (ref "U1") (pin "6") (pinfunction "GPIO6(SDMMC1_CMD)_6") (pintype "bidirectional"))
    )
    (net (code "34") (name "Net-(6_SD_CLK-3)") (class "Default")
      (node (ref "6_SD_CLK") (pin "1") (pinfunction "3_1") (pintype "passive"))
      (node (ref "U1") (pin "7") (pinfunction "GPIO7(SDMMC1_CK)_7") (pintype "bidirectional"))
    )
    (net (code "35") (name "Net-(7_CS-3)") (class "Default")
      (node (ref "7_CS") (pin "1") (pinfunction "3_1") (pintype "passive"))
      (node (ref "U1") (pin "8") (pinfunction "GPIO8(SPI1_NSS)_8") (pintype "bidirectional"))
    )
    (net (code "36") (name "Net-(8_SCK-3)") (class "Default")
      (node (ref "8_SCK") (pin "1") (pinfunction "3_1") (pintype "passive"))
      (node (ref "U1") (pin "9") (pinfunction "GPIO9(SPI1_SCK)_9") (pintype "bidirectional"))
    )
    (net (code "37") (name "Net-(9_MISO-3)") (class "Default")
      (node (ref "9_MISO") (pin "1") (pinfunction "3_1") (pintype "passive"))
      (node (ref "U1") (pin "10") (pinfunction "GPIO10(SPI1_MISO)_10") (pintype "bidirectional"))
    )
    (net (code "38") (name "Net-(10_MOSI-3)") (class "Default")
      (node (ref "10_MOSI") (pin "1") (pinfunction "3_1") (pintype "passive"))
      (node (ref "U1") (pin "11") (pinfunction "GPIO11(SPI1_MOSI)_11") (pintype "bidirectional"))
    )
    (net (code "39") (name "Net-(11-3)") (class "Default")
      (node (ref "11") (pin "1") (pinfunction "3_1") (pintype "passive"))
      (node (ref "U1") (pin "12") (pinfunction "GPIO12(I2C1_SCL)_12") (pintype "bidirectional"))
    )
    (net (code "40") (name "Net-(12-3)") (class "Default")
      (node (ref "12") (pin "1") (pinfunction "3_1") (pintype "passive"))
      (node (ref "U1") (pin "13") (pinfunction "GPIO13(I2C1_SDA)_13") (pintype "bidirectional"))
    )
    (net (code "41") (name "Net-(13_TX-3)") (class "Default")
      (node (ref "13_TX") (pin "1") (pinfunction "3_1") (pintype "passive"))
      (node (ref "U1") (pin "14") (pinfunction "GPIO14(USART1_TX)_14") (pintype "bidirectional"))
    )
    (net (code "42") (name "Net-(14_RX-3)") (class "Default")
      (node (ref "14_RX") (pin "1") (pinfunction "3_1") (pintype "passive"))
      (node (ref "U1") (pin "15") (pinfunction "GPIO15(USART1_RX)_15") (pintype "bidirectional"))
    )
    (net (code "43") (name "Net-(AIN1-3)") (class "Default")
      (node (ref "AIN1") (pin "1") (pinfunction "3_1") (pintype "passive"))
      (node (ref "R7") (pin "1") (pinfunction "1_1") (pintype "passive"))
    )
    (net (code "44") (name "Net-(AIN2-3)") (class "Default")
      (node (ref "AIN2") (pin "1") (pinfunction "3_1") (pintype "passive"))
      (node (ref "R8") (pin "1") (pinfunction "1_1") (pintype "passive"))
    )
    (net (code "45") (name "Net-(AOUT1-3)") (class "Default")
      (node (ref "AOUT1") (pin "1") (pinfunction "3_1") (pintype "passive"))
      (node (ref "R19") (pin "2") (pinfunction "2_2") (pintype "passive"))
    )
    (net (code "46") (name "Net-(AOUT2-3)") (class "Default")
      (node (ref "AOUT2") (pin "1") (pinfunction "3_1") (pintype "passive"))
      (node (ref "R20") (pin "2") (pinfunction "2_2") (pintype "passive"))
    )
    (net (code "47") (name "Net-(CV1A-3)") (class "Default")
      (node (ref "CV1A") (pin "1") (pinfunction "3_1") (pintype "passive"))
      (node (ref "R22") (pin "1") (pinfunction "1_1") (pintype "passive"))
    )
    (net (code "48") (name "Net-(CV1B-3)") (class "Default")
      (node (ref "CV1B") (pin "1") (pinfunction "3_1") (pintype "passive"))
      (node (ref "R23") (pin "1") (pinfunction "1_1") (pintype "passive"))
    )
    (net (code "49") (name "Net-(CV2A-3)") (class "Default")
      (node (ref "CV2A") (pin "1") (pinfunction "3_1") (pintype "passive"))
      (node (ref "R27") (pin "1") (pinfunction "1_1") (pintype "passive"))
    )
    (net (code "50") (name "Net-(CV2B-3)") (class "Default")
      (node (ref "CV2B") (pin "1") (pinfunction "3_1") (pintype "passive"))
      (node (ref "R28") (pin "1") (pinfunction "1_1") (pintype "passive"))
    )
    (net (code "51") (name "Net-(CV3A-3)") (class "Default")
      (node (ref "CV3A") (pin "1") (pinfunction "3_1") (pintype "passive"))
      (node (ref "R31") (pin "1") (pinfunction "1_1") (pintype "passive"))
    )
    (net (code "52") (name "Net-(CV3B-3)") (class "Default")
      (node (ref "CV3B") (pin "1") (pinfunction "3_1") (pintype "passive"))
      (node (ref "R32") (pin "1") (pinfunction "1_1") (pintype "passive"))
    )
    (net (code "53") (name "Net-(CV4A-3)") (class "Default")
      (node (ref "CV4A") (pin "1") (pinfunction "3_1") (pintype "passive"))
      (node (ref "R35") (pin "1") (pinfunction "1_1") (pintype "passive"))
    )
    (net (code "54") (name "Net-(CV4B-3)") (class "Default")
      (node (ref "CV4B") (pin "1") (pinfunction "3_1") (pintype "passive"))
      (node (ref "R36") (pin "1") (pinfunction "1_1") (pintype "passive"))
    )
    (net (code "55") (name "Net-(CV5A-3)") (class "Default")
      (node (ref "CV5A") (pin "1") (pinfunction "3_1") (pintype "passive"))
      (node (ref "R39") (pin "1") (pinfunction "1_1") (pintype "passive"))
    )
    (net (code "56") (name "Net-(CV5B-3)") (class "Default")
      (node (ref "CV5B") (pin "1") (pinfunction "3_1") (pintype "passive"))
      (node (ref "R40") (pin "1") (pinfunction "1_1") (pintype "passive"))
    )
    (net (code "57") (name "Net-(CV6A-3)") (class "Default")
      (node (ref "CV6A") (pin "1") (pinfunction "3_1") (pintype "passive"))
      (node (ref "R44") (pin "1") (pinfunction "1_1") (pintype "passive"))
    )
    (net (code "58") (name "Net-(CV6B-3)") (class "Default")
      (node (ref "CV6B") (pin "1") (pinfunction "3_1") (pintype "passive"))
      (node (ref "R45") (pin "1") (pinfunction "1_1") (pintype "passive"))
    )
    (net (code "59") (name "Net-(CV7A-3)") (class "Default")
      (node (ref "CV7A") (pin "1") (pinfunction "3_1") (pintype "passive"))
      (node (ref "R47") (pin "1") (pinfunction "1_1") (pintype "passive"))
    )
    (net (code "60") (name "Net-(CV7B-3)") (class "Default")
      (node (ref "CV7B") (pin "1") (pinfunction "3_1") (pintype "passive"))
      (node (ref "R48") (pin "1") (pinfunction "1_1") (pintype "passive"))
    )
    (net (code "61") (name "Net-(CV8A-3)") (class "Default")
      (node (ref "CV8A") (pin "1") (pinfunction "3_1") (pintype "passive"))
      (node (ref "R51") (pin "1") (pinfunction "1_1") (pintype "passive"))
    )
    (net (code "62") (name "Net-(CV8B-3)") (class "Default")
      (node (ref "CV8B") (pin "1") (pinfunction "3_1") (pintype "passive"))
      (node (ref "R52") (pin "1") (pinfunction "1_1") (pintype "passive"))
    )
    (net (code "63") (name "Net-(CVOUT1-3)") (class "Default")
      (node (ref "CVOUT1") (pin "1") (pinfunction "3_1") (pintype "passive"))
      (node (ref "R70") (pin "2") (pinfunction "2_2") (pintype "passive"))
    )
    (net (code "64") (name "Net-(CVOUT2-3)") (class "Default")
      (node (ref "CVOUT2") (pin "1") (pinfunction "3_1") (pintype "passive"))
      (node (ref "R71") (pin "2") (pinfunction "2_2") (pintype "passive"))
    )
    (net (code "65") (name "Net-(GTIN1-3)") (class "Default")
      (node (ref "GTIN1") (pin "1") (pinfunction "3_1") (pintype "passive"))
      (node (ref "R55") (pin "1") (pinfunction "1_1") (pintype "passive"))
    )
    (net (code "66") (name "Net-(GTIN2-3)") (class "Default")
      (node (ref "GTIN2") (pin "1") (pinfunction "3_1") (pintype "passive"))
      (node (ref "R59") (pin "1") (pinfunction "1_1") (pintype "passive"))
    )
    (net (code "67") (name "Net-(IC1A--IN)") (class "Default")
      (node (ref "C6") (pin "1") (pinfunction "1_1") (pintype "passive"))
      (node (ref "IC1") (pin "2") (pinfunction "-IN_2") (pintype "input"))
      (node (ref "R4") (pin "1") (pinfunction "1_1") (pintype "passive"))
      (node (ref "R7") (pin "2") (pinfunction "2_2") (pintype "passive"))
    )
    (net (code "68") (name "Net-(IC1A-OUT)") (class "Default")
      (node (ref "C6") (pin "2") (pinfunction "2_2") (pintype "passive"))
      (node (ref "IC1") (pin "1") (pinfunction "OUT_1") (pintype "output"))
      (node (ref "R2") (pin "1") (pinfunction "1_1") (pintype "passive"))
      (node (ref "R4") (pin "2") (pinfunction "2_2") (pintype "passive"))
    )
    (net (code "69") (name "Net-(IC1B--IN)") (class "Default")
      (node (ref "C4") (pin "1") (pinfunction "1_1") (pintype "passive"))
      (node (ref "IC1") (pin "6") (pinfunction "-IN_6") (pintype "input"))
      (node (ref "R2") (pin "2") (pinfunction "2_2") (pintype "passive"))
      (node (ref "R3") (pin "1") (pinfunction "1_1") (pintype "passive"))
    )
    (net (code "70") (name "Net-(IC1B-OUT)") (class "Default")
      (node (ref "C4") (pin "2") (pinfunction "2_2") (pintype "passive"))
      (node (ref "IC1") (pin "7") (pinfunction "OUT_7") (pintype "output"))
      (node (ref "R3") (pin "2") (pinfunction "2_2") (pintype "passive"))
      (node (ref "R9") (pin "1") (pinfunction "1_1") (pintype "passive"))
    )
    (net (code "71") (name "Net-(IC1C--IN)") (class "Default")
      (node (ref "C5") (pin "1") (pinfunction "1_1") (pintype "passive"))
      (node (ref "IC1") (pin "9") (pinfunction "-IN_9") (pintype "input"))
      (node (ref "R1") (pin "2") (pinfunction "2_2") (pintype "passive"))
      (node (ref "R5") (pin "1") (pinfunction "1_1") (pintype "passive"))
    )
    (net (code "72") (name "Net-(IC1C-OUT)") (class "Default")
      (node (ref "C5") (pin "2") (pinfunction "2_2") (pintype "passive"))
      (node (ref "IC1") (pin "8") (pinfunction "OUT_8") (pintype "output"))
      (node (ref "R10") (pin "1") (pinfunction "1_1") (pintype "passive"))
      (node (ref "R5") (pin "2") (pinfunction "2_2") (pintype "passive"))
    )
    (net (code "73") (name "Net-(IC1D--IN)") (class "Default")
      (node (ref "C7") (pin "1") (pinfunction "1_1") (pintype "passive"))
      (node (ref "IC1") (pin "13") (pinfunction "-IN_13") (pintype "input"))
      (node (ref "R6") (pin "1") (pinfunction "1_1") (pintype "passive"))
      (node (ref "R8") (pin "2") (pinfunction "2_2") (pintype "passive"))
    )
    (net (code "74") (name "Net-(IC1D-OUT)") (class "Default")
      (node (ref "C7") (pin "2") (pinfunction "2_2") (pintype "passive"))
      (node (ref "IC1") (pin "14") (pinfunction "OUT_14") (pintype "output"))
      (node (ref "R1") (pin "1") (pinfunction "1_1") (pintype "passive"))
      (node (ref "R6") (pin "2") (pinfunction "2_2") (pintype "passive"))
    )
    (net (code "75") (name "Net-(IC3A--IN)") (class "Default")
      (node (ref "C10") (pin "1") (pinfunction "1_1") (pintype "passive"))
      (node (ref "IC3") (pin "2") (pinfunction "-IN_2") (pintype "input"))
      (node (ref "R12") (pin "2") (pinfunction "2_2") (pintype "passive"))
      (node (ref "R13") (pin "1") (pinfunction "1_1") (pintype "passive"))
    )
    (net (code "76") (name "Net-(IC3A-OUT)") (class "Default")
      (node (ref "C10") (pin "2") (pinfunction "2_2") (pintype "passive"))
      (node (ref "IC3") (pin "1") (pinfunction "OUT_1") (pintype "output"))
      (node (ref "R13") (pin "2") (pinfunction "2_2") (pintype "passive"))
      (node (ref "R19") (pin "1") (pinfunction "1_1") (pintype "passive"))
    )
    (net (code "77") (name "Net-(IC3B--IN)") (class "Default")
      (node (ref "C12") (pin "1") (pinfunction "1_1") (pintype "passive"))
      (node (ref "IC3") (pin "6") (pinfunction "-IN_6") (pintype "input"))
      (node (ref "R14") (pin "1") (pinfunction "1_1") (pintype "passive"))
      (node (ref "R17") (pin "2") (pinfunction "2_2") (pintype "passive"))
    )
    (net (code "78") (name "Net-(IC3B-OUT)") (class "Default")
      (node (ref "C12") (pin "2") (pinfunction "2_2") (pintype "passive"))
      (node (ref "IC3") (pin "7") (pinfunction "OUT_7") (pintype "output"))
      (node (ref "R12") (pin "1") (pinfunction "1_1") (pintype "passive"))
      (node (ref "R14") (pin "2") (pinfunction "2_2") (pintype "passive"))
    )
    (net (code "79") (name "Net-(IC3C--IN)") (class "Default")
      (node (ref "C13") (pin "1") (pinfunction "1_1") (pintype "passive"))
      (node (ref "IC3") (pin "9") (pinfunction "-IN_9") (pintype "input"))
      (node (ref "R16") (pin "1") (pinfunction "1_1") (pintype "passive"))
      (node (ref "R18") (pin "2") (pinfunction "2_2") (pintype "passive"))
    )
    (net (code "80") (name "Net-(IC3C-OUT)") (class "Default")
      (node (ref "C13") (pin "2") (pinfunction "2_2") (pintype "passive"))
      (node (ref "IC3") (pin "8") (pinfunction "OUT_8") (pintype "output"))
      (node (ref "R11") (pin "1") (pinfunction "1_1") (pintype "passive"))
      (node (ref "R16") (pin "2") (pinfunction "2_2") (pintype "passive"))
    )
    (net (code "81") (name "Net-(IC3D--IN)") (class "Default")
      (node (ref "C11") (pin "1") (pinfunction "1_1") (pintype "passive"))
      (node (ref "IC3") (pin "13") (pinfunction "-IN_13") (pintype "input"))
      (node (ref "R11") (pin "2") (pinfunction "2_2") (pintype "passive"))
      (node (ref "R15") (pin "1") (pinfunction "1_1") (pintype "passive"))
    )
    (net (code "82") (name "Net-(IC3D-OUT)") (class "Default")
      (node (ref "C11") (pin "2") (pinfunction "2_2") (pintype "passive"))
      (node (ref "IC3") (pin "14") (pinfunction "OUT_14") (pintype "output"))
      (node (ref "R15") (pin "2") (pinfunction "2_2") (pintype "passive"))
      (node (ref "R20") (pin "1") (pinfunction "1_1") (pintype "passive"))
    )
    (net (code "83") (name "Net-(IC4A--IN)") (class "Default")
      (node (ref "C16") (pin "1") (pinfunction "1_1") (pintype "passive"))
      (node (ref "IC4") (pin "2") (pinfunction "-IN_2") (pintype "input"))
      (node (ref "R21") (pin "1") (pinfunction "1_1") (pintype "passive"))
      (node (ref "R22") (pin "2") (pinfunction "2_2") (pintype "passive"))
      (node (ref "R23") (pin "2") (pinfunction "2_2") (pintype "passive"))
      (node (ref "R24") (pin "2") (pinfunction "2_2") (pintype "passive"))
    )
    (net (code "84") (name "Net-(IC4B--IN)") (class "Default")
      (node (ref "C17") (pin "1") (pinfunction "1_1") (pintype "passive"))
      (node (ref "IC4") (pin "6") (pinfunction "-IN_6") (pintype "input"))
      (node (ref "R25") (pin "1") (pinfunction "1_1") (pintype "passive"))
      (node (ref "R26") (pin "2") (pinfunction "2_2") (pintype "passive"))
      (node (ref "R27") (pin "2") (pinfunction "2_2") (pintype "passive"))
      (node (ref "R28") (pin "2") (pinfunction "2_2") (pintype "passive"))
    )
    (net (code "85") (name "Net-(IC4C--IN)") (class "Default")
      (node (ref "C20") (pin "1") (pinfunction "1_1") (pintype "passive"))
      (node (ref "IC4") (pin "9") (pinfunction "-IN_9") (pintype "input"))
      (node (ref "R30") (pin "1") (pinfunction "1_1") (pintype "passive"))
      (node (ref "R31") (pin "2") (pinfunction "2_2") (pintype "passive"))
      (node (ref "R32") (pin "2") (pinfunction "2_2") (pintype "passive"))
      (node (ref "R33") (pin "2") (pinfunction "2_2") (pintype "passive"))
    )
    (net (code "86") (name "Net-(IC4D--IN)") (class "Default")
      (node (ref "C21") (pin "1") (pinfunction "1_1") (pintype "passive"))
      (node (ref "IC4") (pin "13") (pinfunction "-IN_13") (pintype "input"))
      (node (ref "R34") (pin "1") (pinfunction "1_1") (pintype "passive"))
      (node (ref "R35") (pin "2") (pinfunction "2_2") (pintype "passive"))
      (node (ref "R36") (pin "2") (pinfunction "2_2") (pintype "passive"))
      (node (ref "R37") (pin "2") (pinfunction "2_2") (pintype "passive"))
    )
    (net (code "87") (name "Net-(IC5A--IN)") (class "Default")
      (node (ref "C22") (pin "1") (pinfunction "1_1") (pintype "passive"))
      (node (ref "IC5") (pin "2") (pinfunction "-IN_2") (pintype "input"))
      (node (ref "R38") (pin "1") (pinfunction "1_1") (pintype "passive"))
      (node (ref "R39") (pin "2") (pinfunction "2_2") (pintype "passive"))
      (node (ref "R40") (pin "2") (pinfunction "2_2") (pintype "passive"))
      (node (ref "R41") (pin "2") (pinfunction "2_2") (pintype "passive"))
    )
    (net (code "88") (name "Net-(IC5B--IN)") (class "Default")
      (node (ref "C23") (pin "1") (pinfunction "1_1") (pintype "passive"))
      (node (ref "IC5") (pin "6") (pinfunction "-IN_6") (pintype "input"))
      (node (ref "R42") (pin "1") (pinfunction "1_1") (pintype "passive"))
      (node (ref "R43") (pin "2") (pinfunction "2_2") (pintype "passive"))
      (node (ref "R44") (pin "2") (pinfunction "2_2") (pintype "passive"))
      (node (ref "R45") (pin "2") (pinfunction "2_2") (pintype "passive"))
    )
    (net (code "89") (name "Net-(IC5C--IN)") (class "Default")
      (node (ref "C24") (pin "1") (pinfunction "1_1") (pintype "passive"))
      (node (ref "IC5") (pin "9") (pinfunction "-IN_9") (pintype "input"))
      (node (ref "R46") (pin "1") (pinfunction "1_1") (pintype "passive"))
      (node (ref "R47") (pin "2") (pinfunction "2_2") (pintype "passive"))
      (node (ref "R48") (pin "2") (pinfunction "2_2") (pintype "passive"))
      (node (ref "R49") (pin "2") (pinfunction "2_2") (pintype "passive"))
    )
    (net (code "90") (name "Net-(IC5D--IN)") (class "Default")
      (node (ref "C25") (pin "1") (pinfunction "1_1") (pintype "passive"))
      (node (ref "IC5") (pin "13") (pinfunction "-IN_13") (pintype "input"))
      (node (ref "R50") (pin "1") (pinfunction "1_1") (pintype "passive"))
      (node (ref "R51") (pin "2") (pinfunction "2_2") (pintype "passive"))
      (node (ref "R52") (pin "2") (pinfunction "2_2") (pintype "passive"))
      (node (ref "R53") (pin "2") (pinfunction "2_2") (pintype "passive"))
    )
    (net (code "91") (name "Net-(IC6A--IN)") (class "Default")
      (node (ref "IC6") (pin "2") (pinfunction "-IN_2") (pintype "input"))
      (node (ref "R65") (pin "1") (pinfunction "1_1") (pintype "passive"))
      (node (ref "R68") (pin "2") (pinfunction "2_2") (pintype "passive"))
    )
    (net (code "92") (name "Net-(IC6A-OUT)") (class "Default")
      (node (ref "IC6") (pin "1") (pinfunction "OUT_1") (pintype "output"))
      (node (ref "R63") (pin "1") (pinfunction "1_1") (pintype "passive"))
      (node (ref "R65") (pin "2") (pinfunction "2_2") (pintype "passive"))
    )
    (net (code "93") (name "Net-(IC6B--IN)") (class "Default")
      (node (ref "IC6") (pin "6") (pinfunction "-IN_6") (pintype "input"))
      (node (ref "R63") (pin "2") (pinfunction "2_2") (pintype "passive"))
      (node (ref "R64") (pin "1") (pinfunction "1_1") (pintype "passive"))
    )
    (net (code "94") (name "Net-(IC6B-OUT)") (class "Default")
      (node (ref "IC6") (pin "7") (pinfunction "OUT_7") (pintype "output"))
      (node (ref "R64") (pin "2") (pinfunction "2_2") (pintype "passive"))
      (node (ref "R70") (pin "1") (pinfunction "1_1") (pintype "passive"))
    )
    (net (code "95") (name "Net-(IC6C--IN)") (class "Default")
      (node (ref "IC6") (pin "9") (pinfunction "-IN_9") (pintype "input"))
      (node (ref "R62") (pin "2") (pinfunction "2_2") (pintype "passive"))
      (node (ref "R66") (pin "1") (pinfunction "1_1") (pintype "passive"))
    )
    (net (code "96") (name "Net-(IC6C-OUT)") (class "Default")
      (node (ref "IC6") (pin "8") (pinfunction "OUT_8") (pintype "output"))
      (node (ref "R66") (pin "2") (pinfunction "2_2") (pintype "passive"))
      (node (ref "R71") (pin "1") (pinfunction "1_1") (pintype "passive"))
    )
    (net (code "97") (name "Net-(IC6D--IN)") (class "Default")
      (node (ref "IC6") (pin "13") (pinfunction "-IN_13") (pintype "input"))
      (node (ref "R67") (pin "1") (pinfunction "1_1") (pintype "passive"))
      (node (ref "R69") (pin "2") (pinfunction "2_2") (pintype "passive"))
    )
    (net (code "98") (name "Net-(IC6D-OUT)") (class "Default")
      (node (ref "IC6") (pin "14") (pinfunction "OUT_14") (pintype "output"))
      (node (ref "R62") (pin "1") (pinfunction "1_1") (pintype "passive"))
      (node (ref "R67") (pin "2") (pinfunction "2_2") (pintype "passive"))
    )
    (net (code "99") (name "Net-(Q1-B)") (class "Default")
      (node (ref "Q1") (pin "2") (pinfunction "B_2") (pintype "passive"))
      (node (ref "R55") (pin "2") (pinfunction "2_2") (pintype "passive"))
      (node (ref "R56") (pin "2") (pinfunction "2_2") (pintype "passive"))
    )
    (net (code "100") (name "Net-(Q1-C)") (class "Default")
      (node (ref "Q1") (pin "1") (pinfunction "C_1") (pintype "passive"))
      (node (ref "R54") (pin "1") (pinfunction "1_1") (pintype "passive"))
      (node (ref "R57") (pin "1") (pinfunction "1_1") (pintype "passive"))
    )
    (net (code "101") (name "Net-(Q2-B)") (class "Default")
      (node (ref "Q2") (pin "2") (pinfunction "B_2") (pintype "passive"))
      (node (ref "R59") (pin "2") (pinfunction "2_2") (pintype "passive"))
      (node (ref "R60") (pin "2") (pinfunction "2_2") (pintype "passive"))
    )
    (net (code "102") (name "Net-(Q2-C)") (class "Default")
      (node (ref "Q2") (pin "1") (pinfunction "C_1") (pintype "passive"))
      (node (ref "R58") (pin "1") (pinfunction "1_1") (pintype "passive"))
      (node (ref "R61") (pin "1") (pinfunction "1_1") (pintype "passive"))
    )
  )
)
